# main.net
KiCad netlist of a schematic drawn in Altium Designer
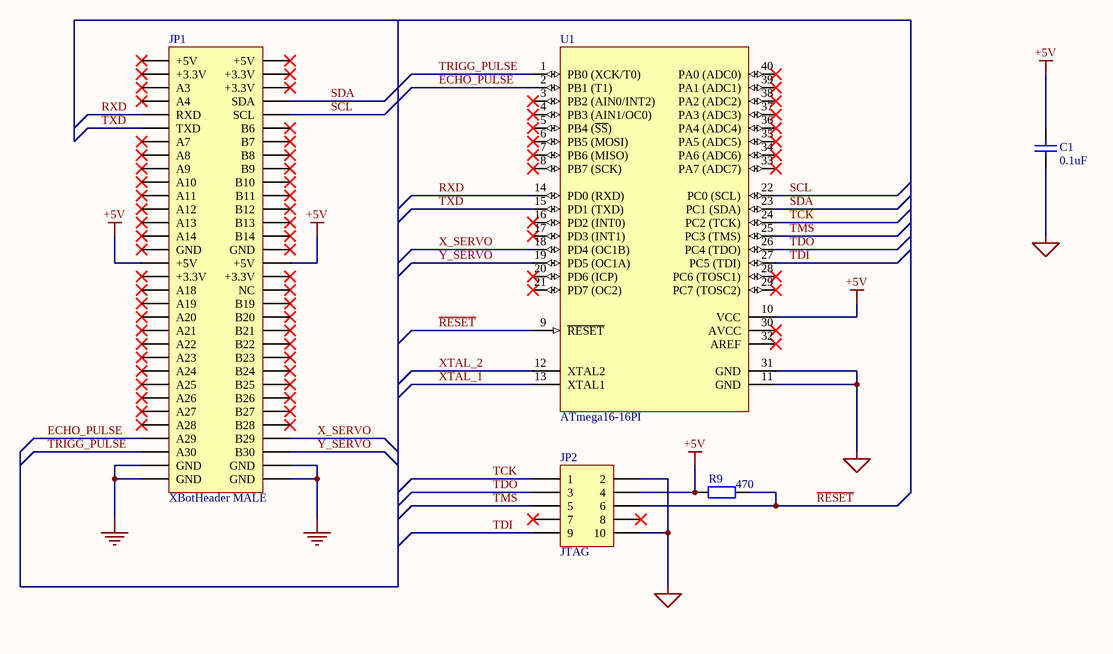
[diagram p0: main.SchDoc]

(export (version "E")
  (design (tool "Eeschema 10.0.6"))
  (components
    (comp (ref "C1")
      (value "0.1uF")
      (footprint "CR2012-0805")
      (description "Capacitor (Semiconductor SIM Model)")
      (fields (field (name "Comment") "Cap Semi_16pF") (field (name "PUBLISHER") "Altium Limited"))
      (libsource (lib "Miscellaneous Devices") (part "Cap Semi"))
    )
    (comp (ref "JP1")
      (value "XBotHeader MALE")
      (footprint "DIN 41 612 - MALE Type B")
      (description "Header, 32-Pin, Dual row")
      (fields (field (name "MANUFACTURER") "Generic Components") (field (name "PUBLISHER") "Altium Limited"))
      (libsource (lib "servo_ranger") (part "XBotHeaderMale"))
    )
    (comp (ref "JP2")
      (value "JTAG")
      (footprint "HDR2X5")
      (description "Header, 5-Pin, Dual row")
      (fields (field (name "PUBLISHER") "Altium Limited"))
      (libsource (lib "Miscellaneous Connectors") (part "Header 5X2"))
    )
    (comp (ref "R9")
      (value "470")
      (footprint "CR2012-0805")
      (description "Semiconductor Resistor")
      (fields (field (name "Comment") "Res Semi") (field (name "PUBLISHER") "Altium Limited"))
      (libsource (lib "Miscellaneous Devices") (part "Res Semi"))
    )
    (comp (ref "U1")
      (value "ATmega16-16PI")
      (footprint "40P6")
      (description "8-Bit AVR Microcontroller with 16K Bytes of In-System Programmable Flash Memory")
      (fields (field (name "PUBLISHER") "Altium Limited"))
      (libsource (lib "Atmel Microcontroller 8-Bit AVR") (part "ATmega16-16PI"))
    )
  )
  (nets
    (net (code "1") (name "+5V") (class "Default")
      (node (ref "C1") (pin "2") (pinfunction "2_2") (pintype "passive"))
      (node (ref "JP1") (pin "A16") (pinfunction "+5V_A16") (pintype "passive"))
      (node (ref "JP1") (pin "B16") (pinfunction "+5V_B16") (pintype "passive"))
      (node (ref "JP2") (pin "4") (pinfunction "4_4") (pintype "passive"))
      (node (ref "R9") (pin "2") (pinfunction "2_2") (pintype "passive"))
      (node (ref "U1") (pin "10") (pinfunction "VCC_10") (pintype "power_in"))
    )
    (net (code "2") (name "/ECHO_PULSE") (class "Default")
      (node (ref "JP1") (pin "A29") (pinfunction "A29_A29") (pintype "passive"))
      (node (ref "U1") (pin "2") (pinfunction "PB1_(T1)_2") (pintype "bidirectional"))
    )
    (net (code "3") (name "/RXD") (class "Default")
      (node (ref "JP1") (pin "A5") (pinfunction "RXD_A5") (pintype "passive"))
      (node (ref "U1") (pin "14") (pinfunction "PD0_(RXD)_14") (pintype "bidirectional"))
    )
    (net (code "4") (name "/SCL") (class "Default")
      (node (ref "JP1") (pin "B5") (pinfunction "SCL_B5") (pintype "passive"))
      (node (ref "U1") (pin "22") (pinfunction "PC0_(SCL)_22") (pintype "bidirectional"))
    )
    (net (code "5") (name "/SDA") (class "Default")
      (node (ref "JP1") (pin "B4") (pinfunction "SDA_B4") (pintype "passive"))
      (node (ref "U1") (pin "23") (pinfunction "PC1_(SDA)_23") (pintype "bidirectional"))
    )
    (net (code "6") (name "/TCK") (class "Default")
      (node (ref "JP2") (pin "1") (pinfunction "1_1") (pintype "passive"))
      (node (ref "U1") (pin "24") (pinfunction "PC2_(TCK)_24") (pintype "bidirectional"))
    )
    (net (code "7") (name "/TDI") (class "Default")
      (node (ref "JP2") (pin "9") (pinfunction "9_9") (pintype "passive"))
      (node (ref "U1") (pin "27") (pinfunction "PC5_(TDI)_27") (pintype "bidirectional"))
    )
    (net (code "8") (name "/TDO") (class "Default")
      (node (ref "JP2") (pin "3") (pinfunction "3_3") (pintype "passive"))
      (node (ref "U1") (pin "26") (pinfunction "PC4_(TDO)_26") (pintype "bidirectional"))
    )
    (net (code "9") (name "/TMS") (class "Default")
      (node (ref "JP2") (pin "5") (pinfunction "5_5") (pintype "passive"))
      (node (ref "U1") (pin "25") (pinfunction "PC3_(TMS)_25") (pintype "bidirectional"))
    )
    (net (code "10") (name "/TRIGG_PULSE") (class "Default")
      (node (ref "JP1") (pin "A30") (pinfunction "A30_A30") (pintype "passive"))
      (node (ref "U1") (pin "1") (pinfunction "PB0_(XCK/T0)_1") (pintype "bidirectional"))
    )
    (net (code "11") (name "/TXD") (class "Default")
      (node (ref "JP1") (pin "A6") (pinfunction "TXD_A6") (pintype "passive"))
      (node (ref "U1") (pin "15") (pinfunction "PD1_(TXD)_15") (pintype "bidirectional"))
    )
    (net (code "12") (name "/XTAL_1") (class "Default")
      (node (ref "U1") (pin "13") (pinfunction "XTAL1_13") (pintype "passive"))
    )
    (net (code "13") (name "/XTAL_2") (class "Default")
      (node (ref "U1") (pin "12") (pinfunction "XTAL2_12") (pintype "passive"))
    )
    (net (code "14") (name "/X_SERVO") (class "Default")
      (node (ref "JP1") (pin "B29") (pinfunction "B29_B29") (pintype "passive"))
      (node (ref "U1") (pin "18") (pinfunction "PD4_(OC1B)_18") (pintype "bidirectional"))
    )
    (net (code "15") (name "/Y_SERVO") (class "Default")
      (node (ref "JP1") (pin "B30") (pinfunction "B30_B30") (pintype "passive"))
      (node (ref "U1") (pin "19") (pinfunction "PD5_(OC1A)_19") (pintype "bidirectional"))
    )
    (net (code "16") (name "/~{RESET}") (class "Default")
      (node (ref "JP2") (pin "6") (pinfunction "6_6") (pintype "passive"))
      (node (ref "R9") (pin "1") (pinfunction "1_1") (pintype "passive"))
      (node (ref "U1") (pin "9") (pinfunction "~{RESET}_9") (pintype "input"))
    )
    (net (code "17") (name "GND") (class "Default")
      (node (ref "C1") (pin "1") (pinfunction "1_1") (pintype "passive"))
      (node (ref "JP1") (pin "A31") (pinfunction "GND_A31") (pintype "passive"))
      (node (ref "JP1") (pin "A32") (pinfunction "GND_A32") (pintype "passive"))
      (node (ref "JP1") (pin "B31") (pinfunction "GND_B31") (pintype "passive"))
      (node (ref "JP1") (pin "B32") (pinfunction "GND_B32") (pintype "passive"))
      (node (ref "JP2") (pin "10") (pinfunction "10_10") (pintype "passive"))
      (node (ref "JP2") (pin "2") (pinfunction "2_2") (pintype "passive"))
      (node (ref "U1") (pin "11") (pinfunction "GND_11") (pintype "power_in"))
      (node (ref "U1") (pin "31") (pinfunction "GND_31") (pintype "power_in"))
    )
    (net (code "18") (name "unconnected-(JP1-+3.3V-PadA2)") (class "Default")
      (node (ref "JP1") (pin "A2") (pinfunction "+3.3V_A2") (pintype "passive+no_connect"))
    )
    (net (code "19") (name "unconnected-(JP1-+3.3V-PadA17)") (class "Default")
      (node (ref "JP1") (pin "A17") (pinfunction "+3.3V_A17") (pintype "passive+no_connect"))
    )
    (net (code "20") (name "unconnected-(JP1-+3.3V-PadB2)") (class "Default")
      (node (ref "JP1") (pin "B2") (pinfunction "+3.3V_B2") (pintype "passive+no_connect"))
    )
    (net (code "21") (name "unconnected-(JP1-+3.3V-PadB3)") (class "Default")
      (node (ref "JP1") (pin "B3") (pinfunction "+3.3V_B3") (pintype "passive+no_connect"))
    )
    (net (code "22") (name "unconnected-(JP1-+3.3V-PadB17)") (class "Default")
      (node (ref "JP1") (pin "B17") (pinfunction "+3.3V_B17") (pintype "passive+no_connect"))
    )
    (net (code "23") (name "unconnected-(JP1-+5V-PadA1)") (class "Default")
      (node (ref "JP1") (pin "A1") (pinfunction "+5V_A1") (pintype "passive+no_connect"))
    )
    (net (code "24") (name "unconnected-(JP1-+5V-PadB1)") (class "Default")
      (node (ref "JP1") (pin "B1") (pinfunction "+5V_B1") (pintype "passive+no_connect"))
    )
    (net (code "25") (name "unconnected-(JP1-GND-PadA15)") (class "Default")
      (node (ref "JP1") (pin "A15") (pinfunction "GND_A15") (pintype "passive+no_connect"))
    )
    (net (code "26") (name "unconnected-(JP1-GND-PadB15)") (class "Default")
      (node (ref "JP1") (pin "B15") (pinfunction "GND_B15") (pintype "passive+no_connect"))
    )
    (net (code "27") (name "unconnected-(JP1-NC-PadB18)") (class "Default")
      (node (ref "JP1") (pin "B18") (pinfunction "NC_B18") (pintype "passive+no_connect"))
    )
    (net (code "28") (name "unconnected-(JP1-PadA3)") (class "Default")
      (node (ref "JP1") (pin "A3") (pinfunction "A3_A3") (pintype "passive+no_connect"))
    )
    (net (code "29") (name "unconnected-(JP1-PadA4)") (class "Default")
      (node (ref "JP1") (pin "A4") (pinfunction "A4_A4") (pintype "passive+no_connect"))
    )
    (net (code "30") (name "unconnected-(JP1-PadA7)") (class "Default")
      (node (ref "JP1") (pin "A7") (pinfunction "A7_A7") (pintype "passive+no_connect"))
    )
    (net (code "31") (name "unconnected-(JP1-PadA8)") (class "Default")
      (node (ref "JP1") (pin "A8") (pinfunction "A8_A8") (pintype "passive+no_connect"))
    )
    (net (code "32") (name "unconnected-(JP1-PadA9)") (class "Default")
      (node (ref "JP1") (pin "A9") (pinfunction "A9_A9") (pintype "passive+no_connect"))
    )
    (net (code "33") (name "unconnected-(JP1-PadA10)") (class "Default")
      (node (ref "JP1") (pin "A10") (pinfunction "A10_A10") (pintype "passive+no_connect"))
    )
    (net (code "34") (name "unconnected-(JP1-PadA11)") (class "Default")
      (node (ref "JP1") (pin "A11") (pinfunction "A11_A11") (pintype "passive+no_connect"))
    )
    (net (code "35") (name "unconnected-(JP1-PadA12)") (class "Default")
      (node (ref "JP1") (pin "A12") (pinfunction "A12_A12") (pintype "passive+no_connect"))
    )
    (net (code "36") (name "unconnected-(JP1-PadA13)") (class "Default")
      (node (ref "JP1") (pin "A13") (pinfunction "A13_A13") (pintype "passive+no_connect"))
    )
    (net (code "37") (name "unconnected-(JP1-PadA14)") (class "Default")
      (node (ref "JP1") (pin "A14") (pinfunction "A14_A14") (pintype "passive+no_connect"))
    )
    (net (code "38") (name "unconnected-(JP1-PadA18)") (class "Default")
      (node (ref "JP1") (pin "A18") (pinfunction "A18_A18") (pintype "passive+no_connect"))
    )
    (net (code "39") (name "unconnected-(JP1-PadA19)") (class "Default")
      (node (ref "JP1") (pin "A19") (pinfunction "A19_A19") (pintype "passive+no_connect"))
    )
    (net (code "40") (name "unconnected-(JP1-PadA20)") (class "Default")
      (node (ref "JP1") (pin "A20") (pinfunction "A20_A20") (pintype "passive+no_connect"))
    )
    (net (code "41") (name "unconnected-(JP1-PadA21)") (class "Default")
      (node (ref "JP1") (pin "A21") (pinfunction "A21_A21") (pintype "passive+no_connect"))
    )
    (net (code "42") (name "unconnected-(JP1-PadA22)") (class "Default")
      (node (ref "JP1") (pin "A22") (pinfunction "A22_A22") (pintype "passive+no_connect"))
    )
    (net (code "43") (name "unconnected-(JP1-PadA23)") (class "Default")
      (node (ref "JP1") (pin "A23") (pinfunction "A23_A23") (pintype "passive+no_connect"))
    )
    (net (code "44") (name "unconnected-(JP1-PadA24)") (class "Default")
      (node (ref "JP1") (pin "A24") (pinfunction "A24_A24") (pintype "passive+no_connect"))
    )
    (net (code "45") (name "unconnected-(JP1-PadA25)") (class "Default")
      (node (ref "JP1") (pin "A25") (pinfunction "A25_A25") (pintype "passive+no_connect"))
    )
    (net (code "46") (name "unconnected-(JP1-PadA26)") (class "Default")
      (node (ref "JP1") (pin "A26") (pinfunction "A26_A26") (pintype "passive+no_connect"))
    )
    (net (code "47") (name "unconnected-(JP1-PadA27)") (class "Default")
      (node (ref "JP1") (pin "A27") (pinfunction "A27_A27") (pintype "passive+no_connect"))
    )
    (net (code "48") (name "unconnected-(JP1-PadA28)") (class "Default")
      (node (ref "JP1") (pin "A28") (pinfunction "A28_A28") (pintype "passive+no_connect"))
    )
    (net (code "49") (name "unconnected-(JP1-PadB6)") (class "Default")
      (node (ref "JP1") (pin "B6") (pinfunction "B6_B6") (pintype "passive+no_connect"))
    )
    (net (code "50") (name "unconnected-(JP1-PadB7)") (class "Default")
      (node (ref "JP1") (pin "B7") (pinfunction "B7_B7") (pintype "passive+no_connect"))
    )
    (net (code "51") (name "unconnected-(JP1-PadB8)") (class "Default")
      (node (ref "JP1") (pin "B8") (pinfunction "B8_B8") (pintype "passive+no_connect"))
    )
    (net (code "52") (name "unconnected-(JP1-PadB9)") (class "Default")
      (node (ref "JP1") (pin "B9") (pinfunction "B9_B9") (pintype "passive+no_connect"))
    )
    (net (code "53") (name "unconnected-(JP1-PadB10)") (class "Default")
      (node (ref "JP1") (pin "B10") (pinfunction "B10_B10") (pintype "passive+no_connect"))
    )
    (net (code "54") (name "unconnected-(JP1-PadB11)") (class "Default")
      (node (ref "JP1") (pin "B11") (pinfunction "B11_B11") (pintype "passive+no_connect"))
    )
    (net (code "55") (name "unconnected-(JP1-PadB12)") (class "Default")
      (node (ref "JP1") (pin "B12") (pinfunction "B12_B12") (pintype "passive+no_connect"))
    )
    (net (code "56") (name "unconnected-(JP1-PadB13)") (class "Default")
      (node (ref "JP1") (pin "B13") (pinfunction "B13_B13") (pintype "passive+no_connect"))
    )
    (net (code "57") (name "unconnected-(JP1-PadB14)") (class "Default")
      (node (ref "JP1") (pin "B14") (pinfunction "B14_B14") (pintype "passive+no_connect"))
    )
    (net (code "58") (name "unconnected-(JP1-PadB19)") (class "Default")
      (node (ref "JP1") (pin "B19") (pinfunction "B19_B19") (pintype "passive+no_connect"))
    )
    (net (code "59") (name "unconnected-(JP1-PadB20)") (class "Default")
      (node (ref "JP1") (pin "B20") (pinfunction "B20_B20") (pintype "passive+no_connect"))
    )
    (net (code "60") (name "unconnected-(JP1-PadB21)") (class "Default")
      (node (ref "JP1") (pin "B21") (pinfunction "B21_B21") (pintype "passive+no_connect"))
    )
    (net (code "61") (name "unconnected-(JP1-PadB22)") (class "Default")
      (node (ref "JP1") (pin "B22") (pinfunction "B22_B22") (pintype "passive+no_connect"))
    )
    (net (code "62") (name "unconnected-(JP1-PadB23)") (class "Default")
      (node (ref "JP1") (pin "B23") (pinfunction "B23_B23") (pintype "passive+no_connect"))
    )
    (net (code "63") (name "unconnected-(JP1-PadB24)") (class "Default")
      (node (ref "JP1") (pin "B24") (pinfunction "B24_B24") (pintype "passive+no_connect"))
    )
    (net (code "64") (name "unconnected-(JP1-PadB25)") (class "Default")
      (node (ref "JP1") (pin "B25") (pinfunction "B25_B25") (pintype "passive+no_connect"))
    )
    (net (code "65") (name "unconnected-(JP1-PadB26)") (class "Default")
      (node (ref "JP1") (pin "B26") (pinfunction "B26_B26") (pintype "passive+no_connect"))
    )
    (net (code "66") (name "unconnected-(JP1-PadB27)") (class "Default")
      (node (ref "JP1") (pin "B27") (pinfunction "B27_B27") (pintype "passive+no_connect"))
    )
    (net (code "67") (name "unconnected-(JP1-PadB28)") (class "Default")
      (node (ref "JP1") (pin "B28") (pinfunction "B28_B28") (pintype "passive+no_connect"))
    )
    (net (code "68") (name "unconnected-(JP2-Pad7)") (class "Default")
      (node (ref "JP2") (pin "7") (pinfunction "7_7") (pintype "passive+no_connect"))
    )
    (net (code "69") (name "unconnected-(JP2-Pad8)") (class "Default")
      (node (ref "JP2") (pin "8") (pinfunction "8_8") (pintype "passive+no_connect"))
    )
    (net (code "70") (name "unconnected-(U1-AREF-Pad32)") (class "Default")
      (node (ref "U1") (pin "32") (pinfunction "AREF_32") (pintype "passive+no_connect"))
    )
    (net (code "71") (name "unconnected-(U1-AVCC-Pad30)") (class "Default")
      (node (ref "U1") (pin "30") (pinfunction "AVCC_30") (pintype "power_in+no_connect"))
    )
    (net (code "72") (name "unconnected-(U1-PA0_(ADC0)-Pad40)") (class "Default")
      (node (ref "U1") (pin "40") (pinfunction "PA0_(ADC0)_40") (pintype "bidirectional+no_connect"))
    )
    (net (code "73") (name "unconnected-(U1-PA1_(ADC1)-Pad39)") (class "Default")
      (node (ref "U1") (pin "39") (pinfunction "PA1_(ADC1)_39") (pintype "bidirectional+no_connect"))
    )
    (net (code "74") (name "unconnected-(U1-PA2_(ADC2)-Pad38)") (class "Default")
      (node (ref "U1") (pin "38") (pinfunction "PA2_(ADC2)_38") (pintype "bidirectional+no_connect"))
    )
    (net (code "75") (name "unconnected-(U1-PA3_(ADC3)-Pad37)") (class "Default")
      (node (ref "U1") (pin "37") (pinfunction "PA3_(ADC3)_37") (pintype "bidirectional+no_connect"))
    )
    (net (code "76") (name "unconnected-(U1-PA4_(ADC4)-Pad36)") (class "Default")
      (node (ref "U1") (pin "36") (pinfunction "PA4_(ADC4)_36") (pintype "bidirectional+no_connect"))
    )
    (net (code "77") (name "unconnected-(U1-PA5_(ADC5)-Pad35)") (class "Default")
      (node (ref "U1") (pin "35") (pinfunction "PA5_(ADC5)_35") (pintype "bidirectional+no_connect"))
    )
    (net (code "78") (name "unconnected-(U1-PA6_(ADC6)-Pad34)") (class "Default")
      (node (ref "U1") (pin "34") (pinfunction "PA6_(ADC6)_34") (pintype "bidirectional+no_connect"))
    )
    (net (code "79") (name "unconnected-(U1-PA7_(ADC7)-Pad33)") (class "Default")
      (node (ref "U1") (pin "33") (pinfunction "PA7_(ADC7)_33") (pintype "bidirectional+no_connect"))
    )
    (net (code "80") (name "unconnected-(U1-PB2_(AIN0{slash}INT2)-Pad3)") (class "Default")
      (node (ref "U1") (pin "3") (pinfunction "PB2_(AIN0/INT2)_3") (pintype "bidirectional+no_connect"))
    )
    (net (code "81") (name "unconnected-(U1-PB3_(AIN1{slash}OC0)-Pad4)") (class "Default")
      (node (ref "U1") (pin "4") (pinfunction "PB3_(AIN1/OC0)_4") (pintype "bidirectional+no_connect"))
    )
    (net (code "82") (name "unconnected-(U1-PB4_(~{SS})-Pad5)") (class "Default")
      (node (ref "U1") (pin "5") (pinfunction "PB4_(~{SS})_5") (pintype "bidirectional+no_connect"))
    )
    (net (code "83") (name "unconnected-(U1-PB5_(MOSI)-Pad6)") (class "Default")
      (node (ref "U1") (pin "6") (pinfunction "PB5_(MOSI)_6") (pintype "bidirectional+no_connect"))
    )
    (net (code "84") (name "unconnected-(U1-PB6_(MISO)-Pad7)") (class "Default")
      (node (ref "U1") (pin "7") (pinfunction "PB6_(MISO)_7") (pintype "bidirectional+no_connect"))
    )
    (net (code "85") (name "unconnected-(U1-PB7_(SCK)-Pad8)") (class "Default")
      (node (ref "U1") (pin "8") (pinfunction "PB7_(SCK)_8") (pintype "bidirectional+no_connect"))
    )
    (net (code "86") (name "unconnected-(U1-PC6_(TOSC1)-Pad28)") (class "Default")
      (node (ref "U1") (pin "28") (pinfunction "PC6_(TOSC1)_28") (pintype "bidirectional+no_connect"))
    )
    (net (code "87") (name "unconnected-(U1-PC7_(TOSC2)-Pad29)") (class "Default")
      (node (ref "U1") (pin "29") (pinfunction "PC7_(TOSC2)_29") (pintype "bidirectional+no_connect"))
    )
    (net (code "88") (name "unconnected-(U1-PD2_(INT0)-Pad16)") (class "Default")
      (node (ref "U1") (pin "16") (pinfunction "PD2_(INT0)_16") (pintype "bidirectional+no_connect"))
    )
    (net (code "89") (name "unconnected-(U1-PD3_(INT1)-Pad17)") (class "Default")
      (node (ref "U1") (pin "17") (pinfunction "PD3_(INT1)_17") (pintype "bidirectional+no_connect"))
    )
    (net (code "90") (name "unconnected-(U1-PD6_(ICP)-Pad20)") (class "Default")
      (node (ref "U1") (pin "20") (pinfunction "PD6_(ICP)_20") (pintype "bidirectional+no_connect"))
    )
    (net (code "91") (name "unconnected-(U1-PD7_(OC2)-Pad21)") (class "Default")
      (node (ref "U1") (pin "21") (pinfunction "PD7_(OC2)_21") (pintype "bidirectional+no_connect"))
    )
  )
)
